# SparkFun_FreeSoC2.net
KiCad netlist of a schematic drawn in EAGLE
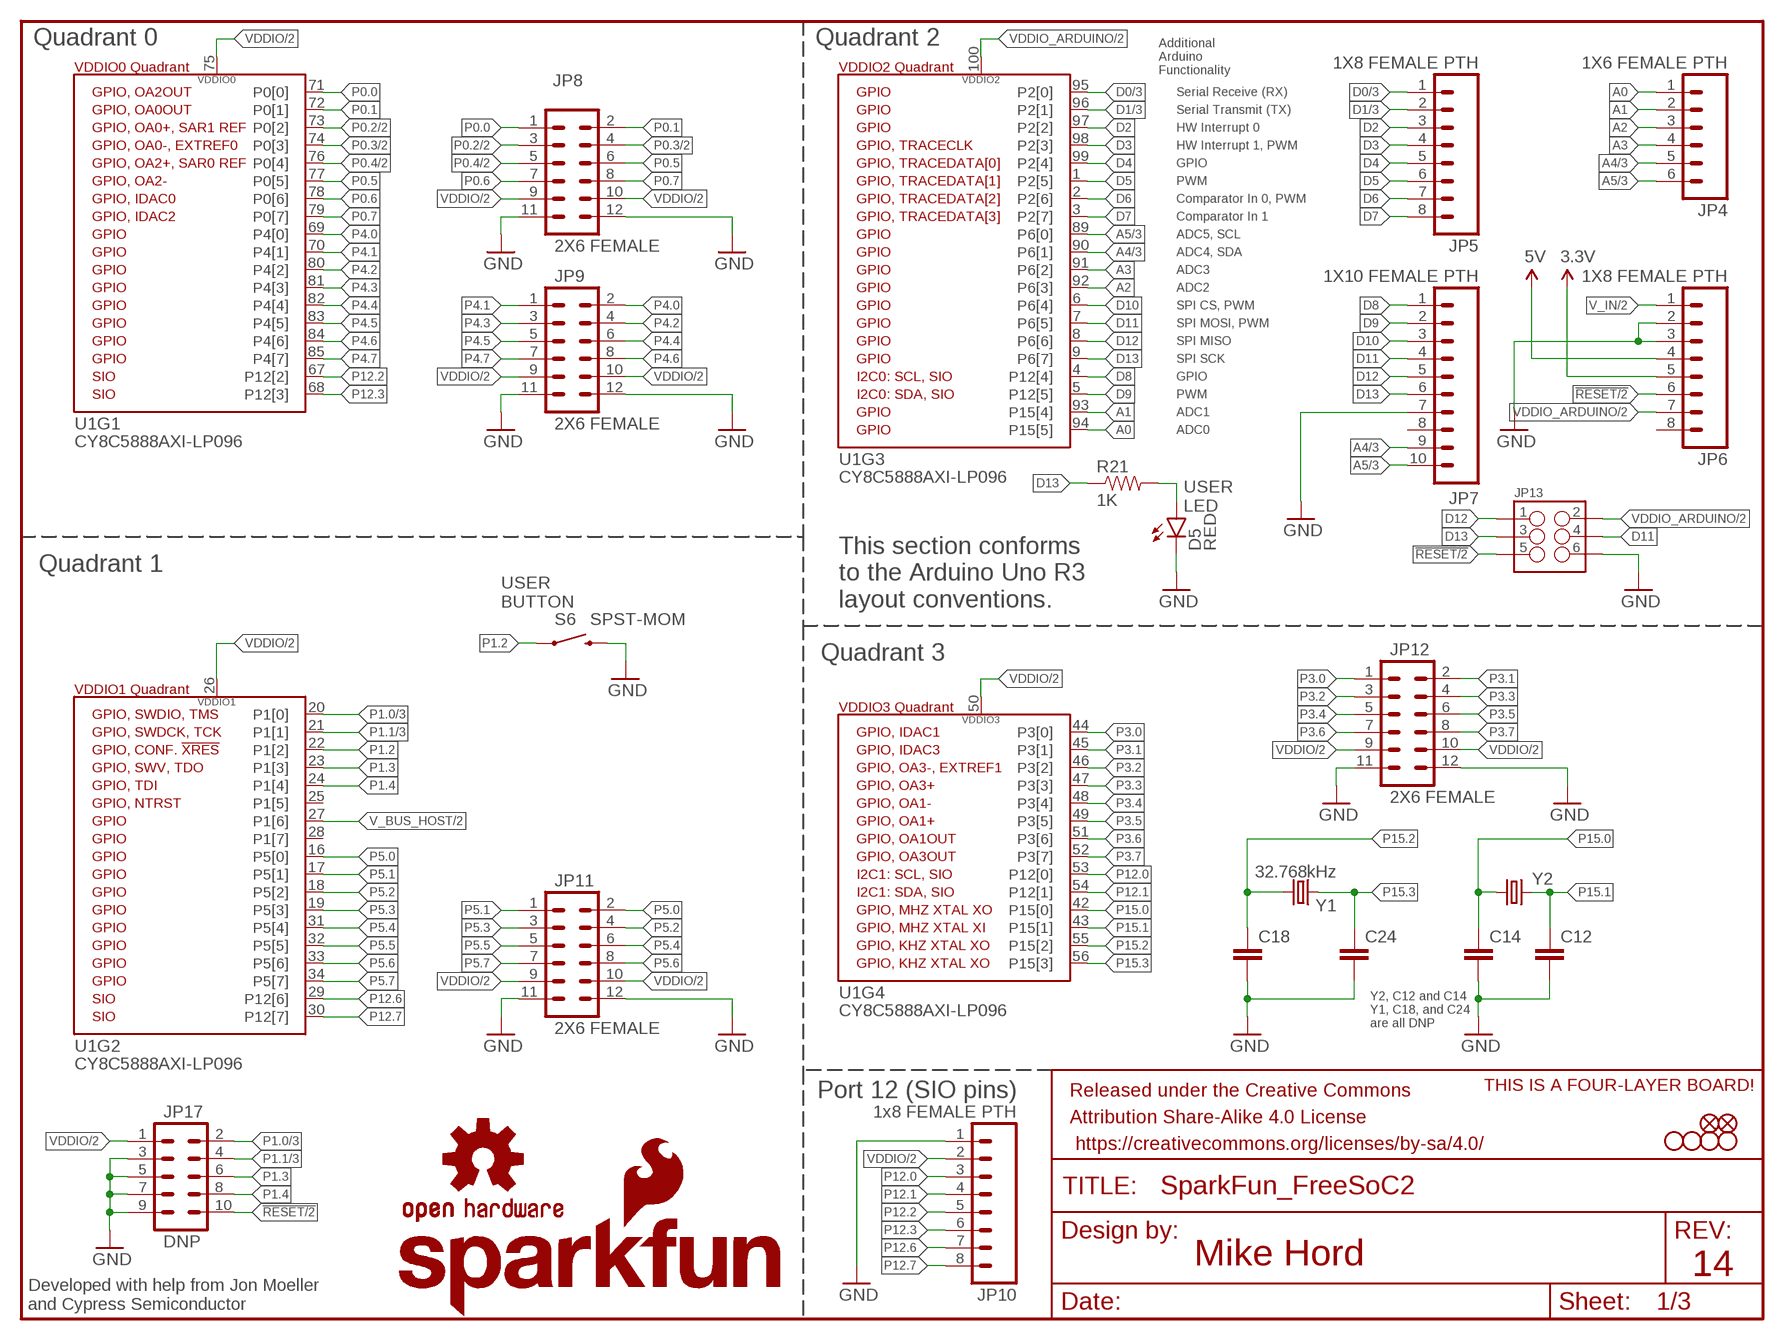
[diagram p0: schematic, sheet 1]
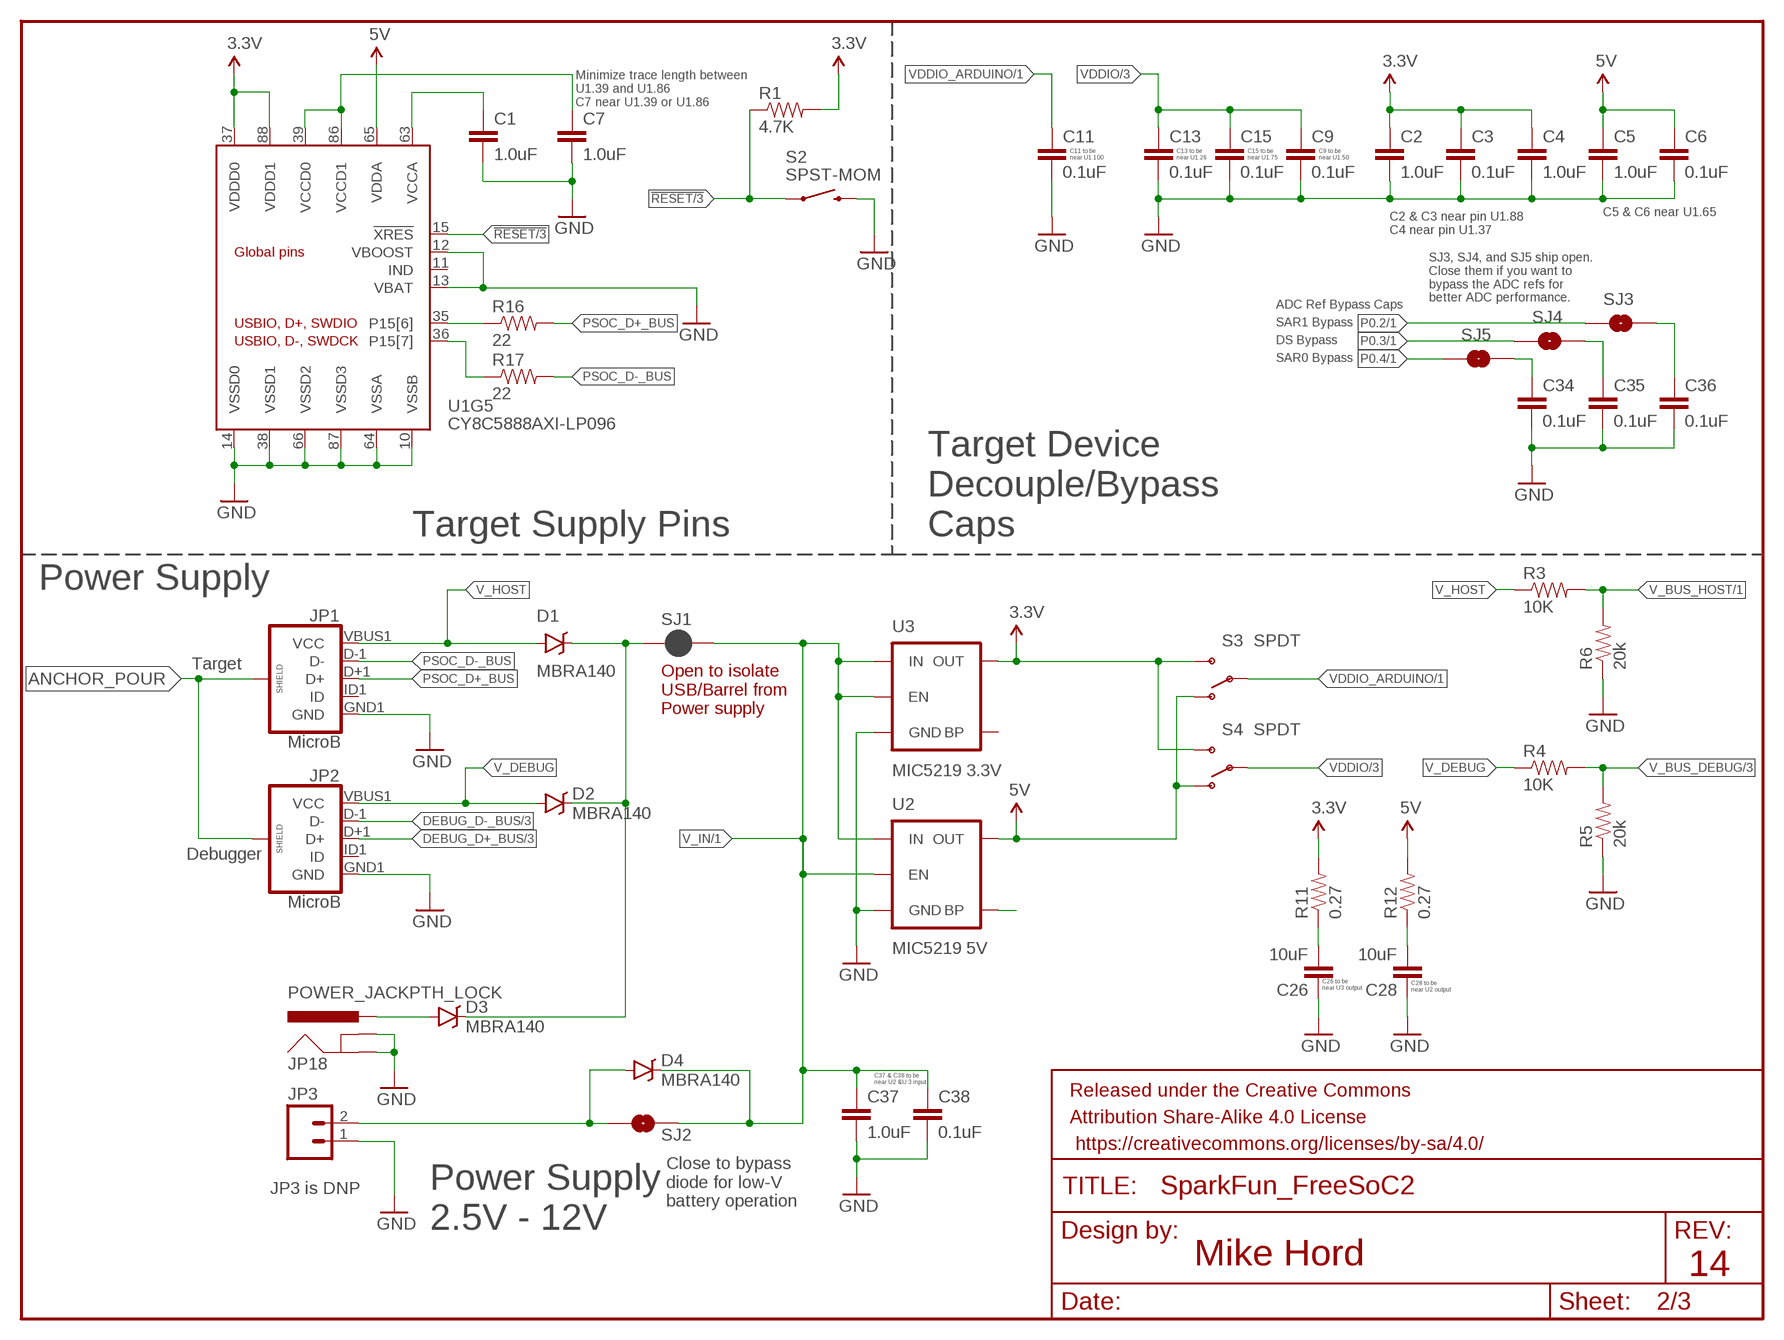
[diagram p1: schematic, sheet 2]
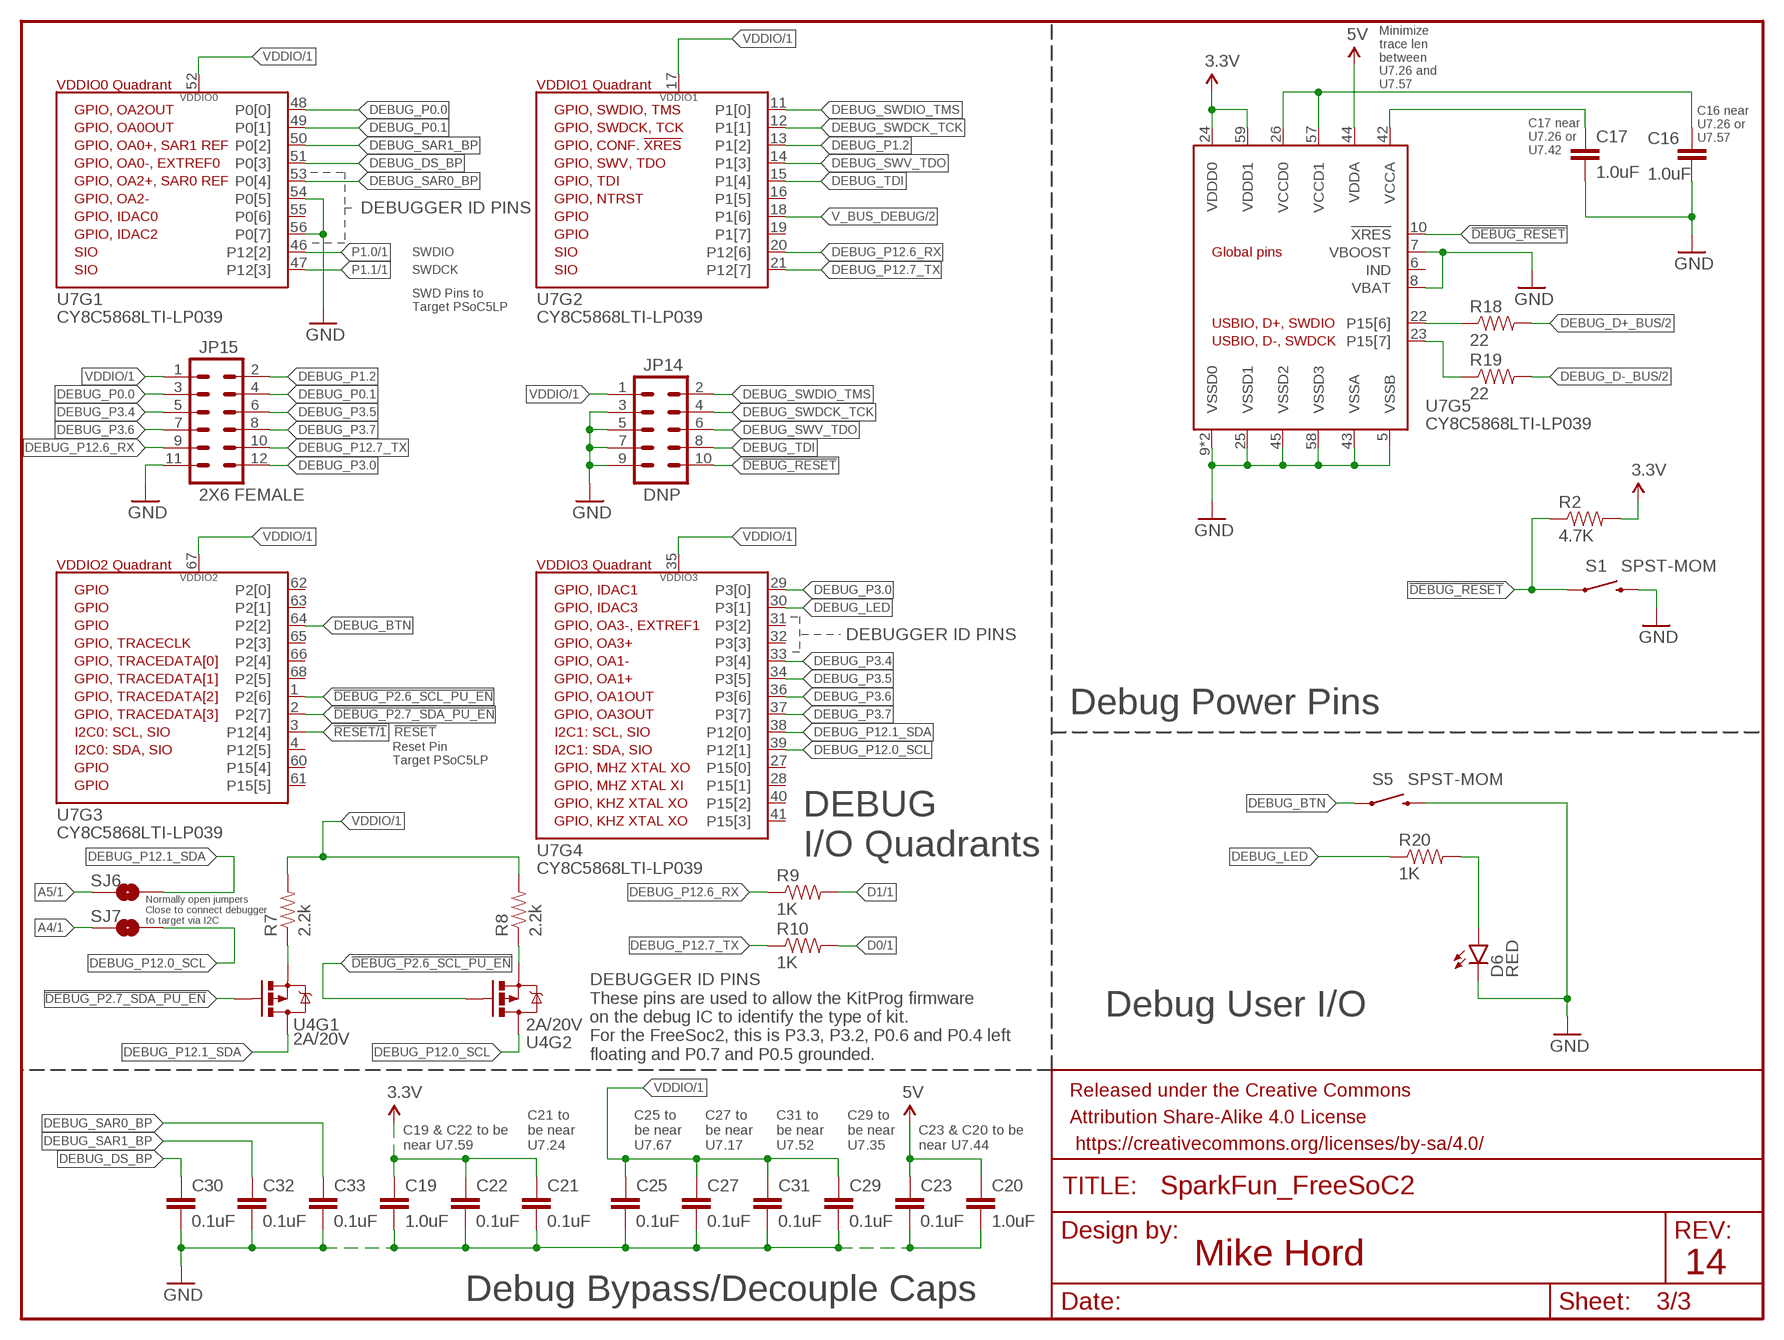
[diagram p2: schematic, sheet 3]

(export (version "E")
  (design (tool "Eeschema 10.0.6"))
  (components
    (comp (ref "C12")
      (value "CAPPTH")
      (footprint "eagle-import:CAP-PTH-SMALL")
      (libsource (lib "eagle-import") (part "CAPPTH"))
    )
    (comp (ref "C14")
      (value "CAPPTH")
      (footprint "eagle-import:CAP-PTH-SMALL")
      (libsource (lib "eagle-import") (part "CAPPTH"))
    )
    (comp (ref "C18")
      (value "CAPPTH")
      (footprint "eagle-import:CAP-PTH-SMALL")
      (libsource (lib "eagle-import") (part "CAPPTH"))
    )
    (comp (ref "C24")
      (value "CAPPTH")
      (footprint "eagle-import:CAP-PTH-SMALL")
      (libsource (lib "eagle-import") (part "CAPPTH"))
    )
    (comp (ref "D5")
      (value "RED")
      (footprint "eagle-import:LED-0603")
      (libsource (lib "eagle-import") (part "LED-RED0603"))
    )
    (comp (ref "FID1")
      (value "FIDUCIAL1X2")
      (footprint "eagle-import:FIDUCIAL-1X2")
      (libsource (lib "eagle-import") (part "FIDUCIAL1X2"))
    )
    (comp (ref "FID2")
      (value "FIDUCIAL1X2")
      (footprint "eagle-import:FIDUCIAL-1X2")
      (libsource (lib "eagle-import") (part "FIDUCIAL1X2"))
    )
    (comp (ref "FRAME3")
      (value "FRAME-LETTERNO_PACKAGE")
      (footprint "eagle-import:DUMMY")
      (fields (field (name "DESIGNER") "Nobody"))
      (libsource (lib "eagle-import") (part "FRAME-LETTERNO_PACKAGE"))
    )
    (comp (ref "JP4")
      (value "1X6 FEMALE PTH")
      (footprint "eagle-import:1X06-SIP_LOCK")
      (libsource (lib "eagle-import") (part "M06SIP_LOCK"))
    )
    (comp (ref "JP5")
      (value "1X8 FEMALE PTH")
      (footprint "eagle-import:1X08_LOCK")
      (libsource (lib "eagle-import") (part "M08LOCK"))
    )
    (comp (ref "JP6")
      (value "1X8 FEMALE PTH")
      (footprint "eagle-import:1X08_LOCK")
      (libsource (lib "eagle-import") (part "M08LOCK"))
    )
    (comp (ref "JP7")
      (value "1X10 FEMALE PTH")
      (footprint "eagle-import:1X10_LOCK")
      (libsource (lib "eagle-import") (part "M10LOCK"))
    )
    (comp (ref "JP8")
      (value "2X6 FEMALE")
      (footprint "eagle-import:2X6")
      (libsource (lib "eagle-import") (part "M06X2PTH_FEMALE"))
    )
    (comp (ref "JP9")
      (value "2X6 FEMALE")
      (footprint "eagle-import:2X6")
      (libsource (lib "eagle-import") (part "M06X2PTH_FEMALE"))
    )
    (comp (ref "JP10")
      (value "1x8 FEMALE PTH")
      (footprint "eagle-import:1X08_LOCK")
      (libsource (lib "eagle-import") (part "M08LOCK"))
    )
    (comp (ref "JP11")
      (value "2X6 FEMALE")
      (footprint "eagle-import:2X6")
      (libsource (lib "eagle-import") (part "M06X2PTH_FEMALE"))
    )
    (comp (ref "JP12")
      (value "2X6 FEMALE")
      (footprint "eagle-import:2X6")
      (libsource (lib "eagle-import") (part "M06X2PTH_FEMALE"))
    )
    (comp (ref "JP13")
      (value "M03X22X3_SILK_MALE_PTH")
      (footprint "eagle-import:2X3")
      (libsource (lib "eagle-import") (part "M03X22X3_SILK_MALE_PTH"))
    )
    (comp (ref "JP17")
      (value "DNP")
      (footprint "eagle-import:2X5_PTH_SILK_.05")
      (libsource (lib "eagle-import") (part "M05X20.05_IN_PTH_SILK"))
    )
    (comp (ref "LOGO1")
      (value "SFE_LOGO_NAME_FLAME.2_INCH")
      (footprint "eagle-import:SFE_LOGO_NAME_FLAME_.2")
      (libsource (lib "eagle-import") (part "SFE_LOGO_NAME_FLAME.2_INCH"))
    )
    (comp (ref "LOGO2")
      (value "OSHW-LOGOS")
      (footprint "eagle-import:OSHW-LOGO-S")
      (libsource (lib "eagle-import") (part "OSHW-LOGOS"))
    )
    (comp (ref "R21")
      (value "1K")
      (footprint "eagle-import:0603-RES@1")
      (libsource (lib "eagle-import") (part "1KOHM1/10W1%(0603)"))
    )
    (comp (ref "S6")
      (value "SPST-MOM")
      (footprint "eagle-import:TACTILE-SWITCH-SMD")
      (libsource (lib "eagle-import") (part "SWITCH-MOMENTARY-2SMD"))
    )
    (comp (ref "STANDOFF1")
      (value "STAND-OFF")
      (footprint "eagle-import:STAND-OFF")
      (libsource (lib "eagle-import") (part "STAND-OFF"))
    )
    (comp (ref "STANDOFF2")
      (value "STAND-OFF")
      (footprint "eagle-import:STAND-OFF")
      (libsource (lib "eagle-import") (part "STAND-OFF"))
    )
    (comp (ref "STANDOFF3")
      (value "STAND-OFF")
      (footprint "eagle-import:STAND-OFF")
      (libsource (lib "eagle-import") (part "STAND-OFF"))
    )
    (comp (ref "STANDOFF4")
      (value "STAND-OFF")
      (footprint "eagle-import:STAND-OFF")
      (libsource (lib "eagle-import") (part "STAND-OFF"))
    )
    (comp (ref "U$1")
      (value "FOUR_LAYER_WARNING")
      (footprint "eagle-import:FOUR_LAYER_WARNING")
      (libsource (lib "eagle-import") (part "FOUR_LAYER_WARNING"))
    )
    (comp (ref "U1")
      (value "CY8C5888AXI-LP096")
      (footprint "eagle-import:TQFP-100-14X14MM")
      (libsource (lib "eagle-import") (part "PSOC_5LP_100QFP"))
    )
    (comp (ref "Y1")
      (value "32.768kHz")
      (footprint "eagle-import:TC26H")
      (libsource (lib "eagle-import") (part "CRYSTALTC26H"))
    )
    (comp (ref "Y2")
      (value "CRYSTALHC49US")
      (footprint "eagle-import:HC49US")
      (libsource (lib "eagle-import") (part "CRYSTALHC49US"))
    )
    (comp (ref "C16")
      (value "1.0uF")
      (footprint "eagle-import:0402-CAP")
      (libsource (lib "eagle-import") (part "1.0UF-16V-10%(0402)"))
    )
    (comp (ref "C17")
      (value "1.0uF")
      (footprint "eagle-import:0402-CAP")
      (libsource (lib "eagle-import") (part "1.0UF-16V-10%(0402)"))
    )
    (comp (ref "C19")
      (value "1.0uF")
      (footprint "eagle-import:0402-CAP")
      (libsource (lib "eagle-import") (part "1.0UF-16V-10%(0402)"))
    )
    (comp (ref "C20")
      (value "1.0uF")
      (footprint "eagle-import:0402-CAP")
      (libsource (lib "eagle-import") (part "1.0UF-16V-10%(0402)"))
    )
    (comp (ref "C21")
      (value "0.1uF")
      (footprint "eagle-import:0402-CAP")
      (libsource (lib "eagle-import") (part "0.1UF-16V(+-10%)(0402)"))
    )
    (comp (ref "C22")
      (value "0.1uF")
      (footprint "eagle-import:0402-CAP")
      (libsource (lib "eagle-import") (part "0.1UF-16V(+-10%)(0402)"))
    )
    (comp (ref "C23")
      (value "0.1uF")
      (footprint "eagle-import:0402-CAP")
      (libsource (lib "eagle-import") (part "0.1UF-16V(+-10%)(0402)"))
    )
    (comp (ref "C25")
      (value "0.1uF")
      (footprint "eagle-import:0402-CAP")
      (libsource (lib "eagle-import") (part "0.1UF-16V(+-10%)(0402)"))
    )
    (comp (ref "C27")
      (value "0.1uF")
      (footprint "eagle-import:0402-CAP")
      (libsource (lib "eagle-import") (part "0.1UF-16V(+-10%)(0402)"))
    )
    (comp (ref "C29")
      (value "0.1uF")
      (footprint "eagle-import:0402-CAP")
      (libsource (lib "eagle-import") (part "0.1UF-16V(+-10%)(0402)"))
    )
    (comp (ref "C30")
      (value "0.1uF")
      (footprint "eagle-import:0402-CAP")
      (libsource (lib "eagle-import") (part "0.1UF-16V(+-10%)(0402)"))
    )
    (comp (ref "C31")
      (value "0.1uF")
      (footprint "eagle-import:0402-CAP")
      (libsource (lib "eagle-import") (part "0.1UF-16V(+-10%)(0402)"))
    )
    (comp (ref "C32")
      (value "0.1uF")
      (footprint "eagle-import:0402-CAP")
      (libsource (lib "eagle-import") (part "0.1UF-16V(+-10%)(0402)"))
    )
    (comp (ref "C33")
      (value "0.1uF")
      (footprint "eagle-import:0402-CAP")
      (libsource (lib "eagle-import") (part "0.1UF-16V(+-10%)(0402)"))
    )
    (comp (ref "D6")
      (value "RED")
      (footprint "eagle-import:LED-0603")
      (libsource (lib "eagle-import") (part "LED-RED0603"))
    )
    (comp (ref "FRAME1")
      (value "FRAME-LETTERNO_PACKAGE")
      (footprint "eagle-import:DUMMY")
      (fields (field (name "DESIGNER") "Nobody"))
      (libsource (lib "eagle-import") (part "FRAME-LETTERNO_PACKAGE"))
    )
    (comp (ref "JP14")
      (value "DNP")
      (footprint "eagle-import:2X5_PTH_SILK_.05")
      (libsource (lib "eagle-import") (part "M05X20.05_IN_PTH_SILK"))
    )
    (comp (ref "JP15")
      (value "2X6 FEMALE")
      (footprint "eagle-import:2X6")
      (libsource (lib "eagle-import") (part "M06X2PTH_FEMALE"))
    )
    (comp (ref "R2")
      (value "4.7K")
      (footprint "eagle-import:0603-RES")
      (libsource (lib "eagle-import") (part "4.7KOHM-1/10W-1%(0603)"))
    )
    (comp (ref "R7")
      (value "2.2k")
      (footprint "eagle-import:0603-RES")
      (libsource (lib "eagle-import") (part "2.2KOHM-1/10W-1%(0603)"))
    )
    (comp (ref "R8")
      (value "2.2k")
      (footprint "eagle-import:0603-RES")
      (libsource (lib "eagle-import") (part "2.2KOHM-1/10W-1%(0603)"))
    )
    (comp (ref "R9")
      (value "1K")
      (footprint "eagle-import:0603-RES@1")
      (libsource (lib "eagle-import") (part "1KOHM1/10W1%(0603)"))
    )
    (comp (ref "R10")
      (value "1K")
      (footprint "eagle-import:0603-RES@1")
      (libsource (lib "eagle-import") (part "1KOHM1/10W1%(0603)"))
    )
    (comp (ref "R18")
      (value "22")
      (footprint "eagle-import:0402-RES")
      (libsource (lib "eagle-import") (part "22OHM1/10W1%(0402)"))
    )
    (comp (ref "R19")
      (value "22")
      (footprint "eagle-import:0402-RES")
      (libsource (lib "eagle-import") (part "22OHM1/10W1%(0402)"))
    )
    (comp (ref "R20")
      (value "1K")
      (footprint "eagle-import:0603-RES@1")
      (libsource (lib "eagle-import") (part "1KOHM1/10W1%(0603)"))
    )
    (comp (ref "S1")
      (value "SPST-MOM")
      (footprint "eagle-import:TACTILE-SWITCH-SMD")
      (libsource (lib "eagle-import") (part "SWITCH-MOMENTARY-2SMD"))
    )
    (comp (ref "S5")
      (value "SPST-MOM")
      (footprint "eagle-import:TACTILE-SWITCH-SMD")
      (libsource (lib "eagle-import") (part "SWITCH-MOMENTARY-2SMD"))
    )
    (comp (ref "SJ6")
      (value "JUMPER-PAD-2-NO")
      (footprint "eagle-import:PAD-JUMPER-2-NO_NO_SILK")
      (libsource (lib "eagle-import") (part "JUMPER-PAD-2-NO"))
    )
    (comp (ref "SJ7")
      (value "JUMPER-PAD-2-NO")
      (footprint "eagle-import:PAD-JUMPER-2-NO_NO_SILK")
      (libsource (lib "eagle-import") (part "JUMPER-PAD-2-NO"))
    )
    (comp (ref "U4")
      (value "2A/20V")
      (footprint "eagle-import:SOT26")
      (libsource (lib "eagle-import") (part "MOSFET-PCHANNEL_DUALSOT26"))
    )
    (comp (ref "U7")
      (value "CY8C5868LTI-LP039")
      (footprint "eagle-import:QFN-68")
      (libsource (lib "eagle-import") (part "PSOC_5LP_68QFN"))
    )
    (comp (ref "C1")
      (value "1.0uF")
      (footprint "eagle-import:0402-CAP")
      (libsource (lib "eagle-import") (part "1.0UF-16V-10%(0402)"))
    )
    (comp (ref "C2")
      (value "1.0uF")
      (footprint "eagle-import:0402-CAP")
      (libsource (lib "eagle-import") (part "1.0UF-16V-10%(0402)"))
    )
    (comp (ref "C3")
      (value "0.1uF")
      (footprint "eagle-import:0402-CAP")
      (libsource (lib "eagle-import") (part "0.1UF-16V(+-10%)(0402)"))
    )
    (comp (ref "C4")
      (value "1.0uF")
      (footprint "eagle-import:0402-CAP")
      (libsource (lib "eagle-import") (part "1.0UF-16V-10%(0402)"))
    )
    (comp (ref "C5")
      (value "1.0uF")
      (footprint "eagle-import:0402-CAP")
      (libsource (lib "eagle-import") (part "1.0UF-16V-10%(0402)"))
    )
    (comp (ref "C6")
      (value "0.1uF")
      (footprint "eagle-import:0402-CAP")
      (libsource (lib "eagle-import") (part "0.1UF-16V(+-10%)(0402)"))
    )
    (comp (ref "C7")
      (value "1.0uF")
      (footprint "eagle-import:0402-CAP")
      (libsource (lib "eagle-import") (part "1.0UF-16V-10%(0402)"))
    )
    (comp (ref "C9")
      (value "0.1uF")
      (footprint "eagle-import:0402-CAP")
      (libsource (lib "eagle-import") (part "0.1UF-16V(+-10%)(0402)"))
    )
    (comp (ref "C11")
      (value "0.1uF")
      (footprint "eagle-import:0402-CAP")
      (libsource (lib "eagle-import") (part "0.1UF-16V(+-10%)(0402)"))
    )
    (comp (ref "C13")
      (value "0.1uF")
      (footprint "eagle-import:0402-CAP")
      (libsource (lib "eagle-import") (part "0.1UF-16V(+-10%)(0402)"))
    )
    (comp (ref "C15")
      (value "0.1uF")
      (footprint "eagle-import:0402-CAP")
      (libsource (lib "eagle-import") (part "0.1UF-16V(+-10%)(0402)"))
    )
    (comp (ref "C26")
      (value "10uF")
      (footprint "eagle-import:0805-CAP")
      (libsource (lib "eagle-import") (part "10UF10V10%(0805)"))
    )
    (comp (ref "C28")
      (value "10uF")
      (footprint "eagle-import:0805-CAP")
      (libsource (lib "eagle-import") (part "10UF10V10%(0805)"))
    )
    (comp (ref "C34")
      (value "0.1uF")
      (footprint "eagle-import:0402-CAP")
      (libsource (lib "eagle-import") (part "0.1UF-16V(+-10%)(0402)"))
    )
    (comp (ref "C35")
      (value "0.1uF")
      (footprint "eagle-import:0402-CAP")
      (libsource (lib "eagle-import") (part "0.1UF-16V(+-10%)(0402)"))
    )
    (comp (ref "C36")
      (value "0.1uF")
      (footprint "eagle-import:0402-CAP")
      (libsource (lib "eagle-import") (part "0.1UF-16V(+-10%)(0402)"))
    )
    (comp (ref "C37")
      (value "1.0uF")
      (footprint "eagle-import:0603-CAP")
      (libsource (lib "eagle-import") (part "1.0UF-16V-10%(0603)"))
    )
    (comp (ref "C38")
      (value "0.1uF")
      (footprint "eagle-import:0603-CAP")
      (libsource (lib "eagle-import") (part "0.1UF-25V(+80/-20%)(0603)"))
    )
    (comp (ref "D1")
      (value "MBRA140")
      (footprint "eagle-import:SMA-DIODE")
      (libsource (lib "eagle-import") (part "MBRA140"))
    )
    (comp (ref "D2")
      (value "MBRA140")
      (footprint "eagle-import:SMA-DIODE")
      (libsource (lib "eagle-import") (part "MBRA140"))
    )
    (comp (ref "D3")
      (value "MBRA140")
      (footprint "eagle-import:SMA-DIODE")
      (libsource (lib "eagle-import") (part "MBRA140"))
    )
    (comp (ref "D4")
      (value "MBRA140")
      (footprint "eagle-import:SMA-DIODE")
      (libsource (lib "eagle-import") (part "MBRA140"))
    )
    (comp (ref "FRAME2")
      (value "FRAME-LETTERNO_PACKAGE")
      (footprint "eagle-import:DUMMY")
      (fields (field (name "DESIGNER") "Nobody"))
      (libsource (lib "eagle-import") (part "FRAME-LETTERNO_PACKAGE"))
    )
    (comp (ref "JP1")
      (value "MicroB")
      (footprint "eagle-import:USB-B-MICRO-SMD_V03")
      (libsource (lib "eagle-import") (part "USB_MICROB_PLUGCONN-11752"))
    )
    (comp (ref "JP2")
      (value "MicroB")
      (footprint "eagle-import:USB-B-MICRO-SMD_V03")
      (libsource (lib "eagle-import") (part "USB_MICROB_PLUGCONN-11752"))
    )
    (comp (ref "JP3")
      (value "M02JST-PTH-2")
      (footprint "eagle-import:JST-2-PTH")
      (libsource (lib "eagle-import") (part "M02JST-PTH-2"))
    )
    (comp (ref "JP18")
      (value "POWER_JACKPTH_LOCK")
      (footprint "eagle-import:POWER_JACK_PTH_LOCK")
      (libsource (lib "eagle-import") (part "POWER_JACKPTH_LOCK"))
    )
    (comp (ref "R1")
      (value "4.7K")
      (footprint "eagle-import:0603-RES")
      (libsource (lib "eagle-import") (part "4.7KOHM-1/10W-1%(0603)"))
    )
    (comp (ref "R3")
      (value "10K")
      (footprint "eagle-import:0603-RES")
      (libsource (lib "eagle-import") (part "10KOHM-1/10W-1%(0603)0603"))
    )
    (comp (ref "R4")
      (value "10K")
      (footprint "eagle-import:0603-RES")
      (libsource (lib "eagle-import") (part "10KOHM-1/10W-1%(0603)0603"))
    )
    (comp (ref "R5")
      (value "20k")
      (footprint "eagle-import:0603-RES")
      (libsource (lib "eagle-import") (part "20KOHM1/10W1%(0603)"))
    )
    (comp (ref "R6")
      (value "20k")
      (footprint "eagle-import:0603-RES")
      (libsource (lib "eagle-import") (part "20KOHM1/10W1%(0603)"))
    )
    (comp (ref "R11")
      (value "0.27")
      (footprint "eagle-import:0603-RES")
      (fields (field (name "PROD_ID") "RES-08787"))
      (libsource (lib "eagle-import") (part "0.27OHM-1/10W-1%(0603)"))
    )
    (comp (ref "R12")
      (value "0.27")
      (footprint "eagle-import:0603-RES")
      (fields (field (name "PROD_ID") "RES-08787"))
      (libsource (lib "eagle-import") (part "0.27OHM-1/10W-1%(0603)"))
    )
    (comp (ref "R16")
      (value "22")
      (footprint "eagle-import:0402-RES")
      (libsource (lib "eagle-import") (part "22OHM1/10W1%(0402)"))
    )
    (comp (ref "R17")
      (value "22")
      (footprint "eagle-import:0402-RES")
      (libsource (lib "eagle-import") (part "22OHM1/10W1%(0402)"))
    )
    (comp (ref "S2")
      (value "SPST-MOM")
      (footprint "eagle-import:TACTILE-SWITCH-SMD")
      (libsource (lib "eagle-import") (part "SWITCH-MOMENTARY-2SMD"))
    )
    (comp (ref "S3")
      (value "SPDT")
      (footprint "eagle-import:SWITCH-SPDT_LOCK.007S")
      (libsource (lib "eagle-import") (part "SWITCH-SPDTPTH_LOCK"))
    )
    (comp (ref "S4")
      (value "SPDT")
      (footprint "eagle-import:SWITCH-SPDT_LOCK.007S")
      (libsource (lib "eagle-import") (part "SWITCH-SPDTPTH_LOCK"))
    )
    (comp (ref "SJ1")
      (value "JUMPER-PAD-2-NC_BY_PASTE")
      (footprint "eagle-import:PAD-JUMPER-2-NC_BY_PASTE_YES_SILK")
      (libsource (lib "eagle-import") (part "JUMPER-PAD-2-NC_BY_PASTE"))
    )
    (comp (ref "SJ2")
      (value "JUMPER-PAD-2-NOYES_SILK")
      (footprint "eagle-import:PAD-JUMPER-2-NO_YES_SILK")
      (libsource (lib "eagle-import") (part "JUMPER-PAD-2-NOYES_SILK"))
    )
    (comp (ref "SJ3")
      (value "JUMPER-PAD-2-NO")
      (footprint "eagle-import:PAD-JUMPER-2-NO_NO_SILK")
      (libsource (lib "eagle-import") (part "JUMPER-PAD-2-NO"))
    )
    (comp (ref "SJ4")
      (value "JUMPER-PAD-2-NO")
      (footprint "eagle-import:PAD-JUMPER-2-NO_NO_SILK")
      (libsource (lib "eagle-import") (part "JUMPER-PAD-2-NO"))
    )
    (comp (ref "SJ5")
      (value "JUMPER-PAD-2-NO")
      (footprint "eagle-import:PAD-JUMPER-2-NO_NO_SILK")
      (libsource (lib "eagle-import") (part "JUMPER-PAD-2-NO"))
    )
    (comp (ref "U2")
      (value "MIC5219 5V")
      (footprint "eagle-import:SOT23-5")
      (libsource (lib "eagle-import") (part "V_REG_MIC52195V"))
    )
    (comp (ref "U3")
      (value "MIC5219 3.3V")
      (footprint "eagle-import:SOT23-5")
      (libsource (lib "eagle-import") (part "V_REG_MIC52193.3V"))
    )
  )
  (nets
    (net (code "1") (name "3.3V") (class "Default")
      (node (ref "C19") (pin "1") (pinfunction "1_1") (pintype "passive"))
      (node (ref "C2") (pin "1") (pinfunction "1_1") (pintype "passive"))
      (node (ref "C21") (pin "1") (pinfunction "1_1") (pintype "passive"))
      (node (ref "C22") (pin "1") (pinfunction "1_1") (pintype "passive"))
      (node (ref "C3") (pin "1") (pinfunction "1_1") (pintype "passive"))
      (node (ref "C4") (pin "1") (pinfunction "1_1") (pintype "passive"))
      (node (ref "JP6") (pin "5") (pinfunction "5_5") (pintype "passive"))
      (node (ref "R1") (pin "2") (pinfunction "2_2") (pintype "passive"))
      (node (ref "R11") (pin "2") (pinfunction "2_2") (pintype "passive"))
      (node (ref "R2") (pin "2") (pinfunction "2_2") (pintype "passive"))
      (node (ref "S3") (pin "3") (pinfunction "S_3") (pintype "passive"))
      (node (ref "S4") (pin "3") (pinfunction "S_3") (pintype "passive"))
      (node (ref "U1") (pin "37") (pinfunction "VDDD0_37") (pintype "bidirectional"))
      (node (ref "U1") (pin "88") (pinfunction "VDDD1_88") (pintype "bidirectional"))
      (node (ref "U3") (pin "5") (pinfunction "OUT_5") (pintype "passive"))
      (node (ref "U7") (pin "24") (pinfunction "VDDD0_24") (pintype "bidirectional"))
      (node (ref "U7") (pin "59") (pinfunction "VDDD1_59") (pintype "bidirectional"))
    )
    (net (code "2") (name "5V") (class "Default")
      (node (ref "C20") (pin "1") (pinfunction "1_1") (pintype "passive"))
      (node (ref "C23") (pin "1") (pinfunction "1_1") (pintype "passive"))
      (node (ref "C5") (pin "1") (pinfunction "1_1") (pintype "passive"))
      (node (ref "C6") (pin "1") (pinfunction "1_1") (pintype "passive"))
      (node (ref "JP6") (pin "4") (pinfunction "4_4") (pintype "passive"))
      (node (ref "R12") (pin "2") (pinfunction "2_2") (pintype "passive"))
      (node (ref "S3") (pin "1") (pinfunction "O_1") (pintype "passive"))
      (node (ref "S4") (pin "1") (pinfunction "O_1") (pintype "passive"))
      (node (ref "U1") (pin "65") (pinfunction "VDDA_65") (pintype "bidirectional"))
      (node (ref "U2") (pin "5") (pinfunction "OUT_5") (pintype "passive"))
      (node (ref "U7") (pin "44") (pinfunction "VDDA_44") (pintype "bidirectional"))
    )
    (net (code "3") (name "A0") (class "Default")
      (node (ref "JP4") (pin "1") (pinfunction "1_1") (pintype "passive"))
      (node (ref "U1") (pin "94") (pinfunction "P15[5]_94") (pintype "bidirectional"))
    )
    (net (code "4") (name "A1") (class "Default")
      (node (ref "JP4") (pin "2") (pinfunction "2_2") (pintype "passive"))
      (node (ref "U1") (pin "93") (pinfunction "P15[4]_93") (pintype "bidirectional"))
    )
    (net (code "5") (name "A2") (class "Default")
      (node (ref "JP4") (pin "3") (pinfunction "3_3") (pintype "passive"))
      (node (ref "U1") (pin "92") (pinfunction "P6[3]_92") (pintype "bidirectional"))
    )
    (net (code "6") (name "A3") (class "Default")
      (node (ref "JP4") (pin "4") (pinfunction "4_4") (pintype "passive"))
      (node (ref "U1") (pin "91") (pinfunction "P6[2]_91") (pintype "bidirectional"))
    )
    (net (code "7") (name "A4") (class "Default")
      (node (ref "JP4") (pin "5") (pinfunction "5_5") (pintype "passive"))
      (node (ref "JP7") (pin "9") (pinfunction "9_9") (pintype "passive"))
      (node (ref "SJ7") (pin "1") (pinfunction "1_1") (pintype "passive"))
      (node (ref "U1") (pin "90") (pinfunction "P6[1]_90") (pintype "bidirectional"))
    )
    (net (code "8") (name "A5") (class "Default")
      (node (ref "JP4") (pin "6") (pinfunction "6_6") (pintype "passive"))
      (node (ref "JP7") (pin "10") (pinfunction "10_10") (pintype "passive"))
      (node (ref "SJ6") (pin "1") (pinfunction "1_1") (pintype "passive"))
      (node (ref "U1") (pin "89") (pinfunction "P6[0]_89") (pintype "bidirectional"))
    )
    (net (code "9") (name "ANCHOR_POUR") (class "Default")
      (node (ref "JP1") (pin "SHIELD1") (pinfunction "SHIELD_SHIELD1") (pintype "bidirectional"))
      (node (ref "JP1") (pin "SHIELD2") (pinfunction "SHIELD_SHIELD2") (pintype "bidirectional"))
      (node (ref "JP1") (pin "SHIELD3") (pinfunction "SHIELD_SHIELD3") (pintype "bidirectional"))
      (node (ref "JP2") (pin "SHIELD1") (pinfunction "SHIELD_SHIELD1") (pintype "bidirectional"))
      (node (ref "JP2") (pin "SHIELD2") (pinfunction "SHIELD_SHIELD2") (pintype "bidirectional"))
      (node (ref "JP2") (pin "SHIELD3") (pinfunction "SHIELD_SHIELD3") (pintype "bidirectional"))
    )
    (net (code "10") (name "D0") (class "Default")
      (node (ref "JP5") (pin "1") (pinfunction "1_1") (pintype "passive"))
      (node (ref "R10") (pin "2") (pinfunction "2_2") (pintype "passive"))
      (node (ref "U1") (pin "95") (pinfunction "P2[0]_95") (pintype "bidirectional"))
    )
    (net (code "11") (name "D1") (class "Default")
      (node (ref "JP5") (pin "2") (pinfunction "2_2") (pintype "passive"))
      (node (ref "R9") (pin "2") (pinfunction "2_2") (pintype "passive"))
      (node (ref "U1") (pin "96") (pinfunction "P2[1]_96") (pintype "bidirectional"))
    )
    (net (code "12") (name "D2") (class "Default")
      (node (ref "JP5") (pin "3") (pinfunction "3_3") (pintype "passive"))
      (node (ref "U1") (pin "97") (pinfunction "P2[2]_97") (pintype "bidirectional"))
    )
    (net (code "13") (name "D3") (class "Default")
      (node (ref "JP5") (pin "4") (pinfunction "4_4") (pintype "passive"))
      (node (ref "U1") (pin "98") (pinfunction "P2[3]_98") (pintype "bidirectional"))
    )
    (net (code "14") (name "D4") (class "Default")
      (node (ref "JP5") (pin "5") (pinfunction "5_5") (pintype "passive"))
      (node (ref "U1") (pin "99") (pinfunction "P2[4]_99") (pintype "bidirectional"))
    )
    (net (code "15") (name "D5") (class "Default")
      (node (ref "JP5") (pin "6") (pinfunction "6_6") (pintype "passive"))
      (node (ref "U1") (pin "1") (pinfunction "P2[5]_1") (pintype "bidirectional"))
    )
    (net (code "16") (name "D6") (class "Default")
      (node (ref "JP5") (pin "7") (pinfunction "7_7") (pintype "passive"))
      (node (ref "U1") (pin "2") (pinfunction "P2[6]_2") (pintype "bidirectional"))
    )
    (net (code "17") (name "D7") (class "Default")
      (node (ref "JP5") (pin "8") (pinfunction "8_8") (pintype "passive"))
      (node (ref "U1") (pin "3") (pinfunction "P2[7]_3") (pintype "bidirectional"))
    )
    (net (code "18") (name "D8") (class "Default")
      (node (ref "JP7") (pin "1") (pinfunction "1_1") (pintype "passive"))
      (node (ref "U1") (pin "4") (pinfunction "P12[4]_4") (pintype "bidirectional"))
    )
    (net (code "19") (name "D9") (class "Default")
      (node (ref "JP7") (pin "2") (pinfunction "2_2") (pintype "passive"))
      (node (ref "U1") (pin "5") (pinfunction "P12[5]_5") (pintype "bidirectional"))
    )
    (net (code "20") (name "D10") (class "Default")
      (node (ref "JP7") (pin "3") (pinfunction "3_3") (pintype "passive"))
      (node (ref "U1") (pin "6") (pinfunction "P6[4]_6") (pintype "bidirectional"))
    )
    (net (code "21") (name "D11") (class "Default")
      (node (ref "JP13") (pin "4") (pinfunction "4_4") (pintype "bidirectional"))
      (node (ref "JP7") (pin "4") (pinfunction "4_4") (pintype "passive"))
      (node (ref "U1") (pin "7") (pinfunction "P6[5]_7") (pintype "bidirectional"))
    )
    (net (code "22") (name "D12") (class "Default")
      (node (ref "JP13") (pin "1") (pinfunction "1_1") (pintype "bidirectional"))
      (node (ref "JP7") (pin "5") (pinfunction "5_5") (pintype "passive"))
      (node (ref "U1") (pin "8") (pinfunction "P6[6]_8") (pintype "bidirectional"))
    )
    (net (code "23") (name "D13") (class "Default")
      (node (ref "JP13") (pin "3") (pinfunction "3_3") (pintype "bidirectional"))
      (node (ref "JP7") (pin "6") (pinfunction "6_6") (pintype "passive"))
      (node (ref "R21") (pin "1") (pinfunction "1_1") (pintype "passive"))
      (node (ref "U1") (pin "9") (pinfunction "P6[7]_9") (pintype "bidirectional"))
    )
    (net (code "24") (name "DEBUG_BTN") (class "Default")
      (node (ref "S5") (pin "1") (pinfunction "1_1") (pintype "passive"))
      (node (ref "U7") (pin "64") (pinfunction "P2[2]_64") (pintype "bidirectional"))
    )
    (net (code "25") (name "DEBUG_D+_BUS") (class "Default")
      (node (ref "JP2") (pin "D+1") (pinfunction "D+_D+1") (pintype "bidirectional"))
      (node (ref "R18") (pin "2") (pinfunction "2_2") (pintype "passive"))
    )
    (net (code "26") (name "DEBUG_D-_BUS") (class "Default")
      (node (ref "JP2") (pin "D-1") (pinfunction "D-_D-1") (pintype "bidirectional"))
      (node (ref "R19") (pin "2") (pinfunction "2_2") (pintype "passive"))
    )
    (net (code "27") (name "DEBUG_DS_BP") (class "Default")
      (node (ref "C30") (pin "1") (pinfunction "1_1") (pintype "passive"))
      (node (ref "U7") (pin "51") (pinfunction "P0[3]_51") (pintype "bidirectional"))
    )
    (net (code "28") (name "DEBUG_LED") (class "Default")
      (node (ref "R20") (pin "1") (pinfunction "1_1") (pintype "passive"))
      (node (ref "U7") (pin "30") (pinfunction "P3[1]_30") (pintype "bidirectional"))
    )
    (net (code "29") (name "DEBUG_P0.0") (class "Default")
      (node (ref "JP15") (pin "3") (pinfunction "3_3") (pintype "passive"))
      (node (ref "U7") (pin "48") (pinfunction "P0[0]_48") (pintype "bidirectional"))
    )
    (net (code "30") (name "DEBUG_P0.1") (class "Default")
      (node (ref "JP15") (pin "4") (pinfunction "4_4") (pintype "passive"))
      (node (ref "U7") (pin "49") (pinfunction "P0[1]_49") (pintype "bidirectional"))
    )
    (net (code "31") (name "DEBUG_P1.2") (class "Default")
      (node (ref "JP15") (pin "2") (pinfunction "2_2") (pintype "passive"))
      (node (ref "U7") (pin "13") (pinfunction "P1[2]_13") (pintype "bidirectional"))
    )
    (net (code "32") (name "DEBUG_P3.0") (class "Default")
      (node (ref "JP15") (pin "12") (pinfunction "12_12") (pintype "passive"))
      (node (ref "U7") (pin "29") (pinfunction "P3[0]_29") (pintype "bidirectional"))
    )
    (net (code "33") (name "DEBUG_P3.4") (class "Default")
      (node (ref "JP15") (pin "5") (pinfunction "5_5") (pintype "passive"))
      (node (ref "U7") (pin "33") (pinfunction "P3[4]_33") (pintype "bidirectional"))
    )
    (net (code "34") (name "DEBUG_P3.5") (class "Default")
      (node (ref "JP15") (pin "6") (pinfunction "6_6") (pintype "passive"))
      (node (ref "U7") (pin "34") (pinfunction "P3[5]_34") (pintype "bidirectional"))
    )
    (net (code "35") (name "DEBUG_P3.6") (class "Default")
      (node (ref "JP15") (pin "7") (pinfunction "7_7") (pintype "passive"))
      (node (ref "U7") (pin "36") (pinfunction "P3[6]_36") (pintype "bidirectional"))
    )
    (net (code "36") (name "DEBUG_P3.7") (class "Default")
      (node (ref "JP15") (pin "8") (pinfunction "8_8") (pintype "passive"))
      (node (ref "U7") (pin "37") (pinfunction "P3[7]_37") (pintype "bidirectional"))
    )
    (net (code "37") (name "DEBUG_P12.0_SCL") (class "Default")
      (node (ref "SJ7") (pin "2") (pinfunction "2_2") (pintype "passive"))
      (node (ref "U4") (pin "D2") (pinfunction "D_D2") (pintype "passive"))
      (node (ref "U7") (pin "39") (pinfunction "P12[1]_39") (pintype "bidirectional"))
    )
    (net (code "38") (name "DEBUG_P12.1_SDA") (class "Default")
      (node (ref "SJ6") (pin "2") (pinfunction "2_2") (pintype "passive"))
      (node (ref "U4") (pin "D1") (pinfunction "D_D1") (pintype "passive"))
      (node (ref "U7") (pin "38") (pinfunction "P12[0]_38") (pintype "bidirectional"))
    )
    (net (code "39") (name "DEBUG_P12.6_RX") (class "Default")
      (node (ref "JP15") (pin "9") (pinfunction "9_9") (pintype "passive"))
      (node (ref "R9") (pin "1") (pinfunction "1_1") (pintype "passive"))
      (node (ref "U7") (pin "20") (pinfunction "P12[6]_20") (pintype "bidirectional"))
    )
    (net (code "40") (name "DEBUG_P12.7_TX") (class "Default")
      (node (ref "JP15") (pin "10") (pinfunction "10_10") (pintype "passive"))
      (node (ref "R10") (pin "1") (pinfunction "1_1") (pintype "passive"))
      (node (ref "U7") (pin "21") (pinfunction "P12[7]_21") (pintype "bidirectional"))
    )
    (net (code "41") (name "DEBUG_SAR0_BP") (class "Default")
      (node (ref "C33") (pin "1") (pinfunction "1_1") (pintype "passive"))
      (node (ref "U7") (pin "53") (pinfunction "P0[4]_53") (pintype "bidirectional"))
    )
    (net (code "42") (name "DEBUG_SAR1_BP") (class "Default")
      (node (ref "C32") (pin "1") (pinfunction "1_1") (pintype "passive"))
      (node (ref "U7") (pin "50") (pinfunction "P0[2]_50") (pintype "bidirectional"))
    )
    (net (code "43") (name "DEBUG_SWDCK_TCK") (class "Default")
      (node (ref "JP14") (pin "4") (pinfunction "4_4") (pintype "passive"))
      (node (ref "U7") (pin "12") (pinfunction "P1[1]_12") (pintype "bidirectional"))
    )
    (net (code "44") (name "DEBUG_SWDIO_TMS") (class "Default")
      (node (ref "JP14") (pin "2") (pinfunction "2_2") (pintype "passive"))
      (node (ref "U7") (pin "11") (pinfunction "P1[0]_11") (pintype "bidirectional"))
    )
    (net (code "45") (name "DEBUG_SWV_TDO") (class "Default")
      (node (ref "JP14") (pin "6") (pinfunction "6_6") (pintype "passive"))
      (node (ref "U7") (pin "14") (pinfunction "P1[3]_14") (pintype "bidirectional"))
    )
    (net (code "46") (name "DEBUG_TDI") (class "Default")
      (node (ref "JP14") (pin "8") (pinfunction "8_8") (pintype "passive"))
      (node (ref "U7") (pin "15") (pinfunction "P1[4]_15") (pintype "bidirectional"))
    )
    (net (code "47") (name "GND") (class "Default")
      (node (ref "C1") (pin "2") (pinfunction "2_2") (pintype "passive"))
      (node (ref "C11") (pin "2") (pinfunction "2_2") (pintype "passive"))
      (node (ref "C12") (pin "2") (pinfunction "2_2") (pintype "passive"))
      (node (ref "C13") (pin "2") (pinfunction "2_2") (pintype "passive"))
      (node (ref "C14") (pin "2") (pinfunction "2_2") (pintype "passive"))
      (node (ref "C15") (pin "2") (pinfunction "2_2") (pintype "passive"))
      (node (ref "C16") (pin "2") (pinfunction "2_2") (pintype "passive"))
      (node (ref "C17") (pin "2") (pinfunction "2_2") (pintype "passive"))
      (node (ref "C18") (pin "2") (pinfunction "2_2") (pintype "passive"))
      (node (ref "C19") (pin "2") (pinfunction "2_2") (pintype "passive"))
      (node (ref "C2") (pin "2") (pinfunction "2_2") (pintype "passive"))
      (node (ref "C20") (pin "2") (pinfunction "2_2") (pintype "passive"))
      (node (ref "C21") (pin "2") (pinfunction "2_2") (pintype "passive"))
      (node (ref "C22") (pin "2") (pinfunction "2_2") (pintype "passive"))
      (node (ref "C23") (pin "2") (pinfunction "2_2") (pintype "passive"))
      (node (ref "C24") (pin "2") (pinfunction "2_2") (pintype "passive"))
      (node (ref "C25") (pin "2") (pinfunction "2_2") (pintype "passive"))
      (node (ref "C26") (pin "1") (pinfunction "1_1") (pintype "passive"))
      (node (ref "C27") (pin "2") (pinfunction "2_2") (pintype "passive"))
      (node (ref "C28") (pin "1") (pinfunction "1_1") (pintype "passive"))
      (node (ref "C29") (pin "2") (pinfunction "2_2") (pintype "passive"))
      (node (ref "C3") (pin "2") (pinfunction "2_2") (pintype "passive"))
      (node (ref "C30") (pin "2") (pinfunction "2_2") (pintype "passive"))
      (node (ref "C31") (pin "2") (pinfunction "2_2") (pintype "passive"))
      (node (ref "C32") (pin "2") (pinfunction "2_2") (pintype "passive"))
      (node (ref "C33") (pin "2") (pinfunction "2_2") (pintype "passive"))
      (node (ref "C34") (pin "2") (pinfunction "2_2") (pintype "passive"))
      (node (ref "C35") (pin "2") (pinfunction "2_2") (pintype "passive"))
      (node (ref "C36") (pin "2") (pinfunction "2_2") (pintype "passive"))
      (node (ref "C37") (pin "2") (pinfunction "2_2") (pintype "passive"))
      (node (ref "C38") (pin "2") (pinfunction "2_2") (pintype "passive"))
      (node (ref "C4") (pin "2") (pinfunction "2_2") (pintype "passive"))
      (node (ref "C5") (pin "2") (pinfunction "2_2") (pintype "passive"))
      (node (ref "C6") (pin "2") (pinfunction "2_2") (pintype "passive"))
      (node (ref "C7") (pin "2") (pinfunction "2_2") (pintype "passive"))
      (node (ref "C9") (pin "2") (pinfunction "2_2") (pintype "passive"))
      (node (ref "D5") (pin "C") (pinfunction "C_C") (pintype "passive"))
      (node (ref "D6") (pin "C") (pinfunction "C_C") (pintype "passive"))
      (node (ref "JP1") (pin "GND1") (pinfunction "GND_GND1") (pintype "bidirectional"))
      (node (ref "JP10") (pin "1") (pinfunction "1_1") (pintype "passive"))
      (node (ref "JP11") (pin "11") (pinfunction "11_11") (pintype "passive"))
      (node (ref "JP11") (pin "12") (pinfunction "12_12") (pintype "passive"))
      (node (ref "JP12") (pin "11") (pinfunction "11_11") (pintype "passive"))
      (node (ref "JP12") (pin "12") (pinfunction "12_12") (pintype "passive"))
      (node (ref "JP13") (pin "6") (pinfunction "6_6") (pintype "bidirectional"))
      (node (ref "JP14") (pin "3") (pinfunction "3_3") (pintype "passive"))
      (node (ref "JP14") (pin "5") (pinfunction "5_5") (pintype "passive"))
      (node (ref "JP14") (pin "7") (pinfunction "7_7") (pintype "passive"))
      (node (ref "JP14") (pin "9") (pinfunction "9_9") (pintype "passive"))
      (node (ref "JP15") (pin "11") (pinfunction "11_11") (pintype "passive"))
      (node (ref "JP17") (pin "3") (pinfunction "3_3") (pintype "passive"))
      (node (ref "JP17") (pin "5") (pinfunction "5_5") (pintype "passive"))
      (node (ref "JP17") (pin "7") (pinfunction "7_7") (pintype "passive"))
      (node (ref "JP17") (pin "9") (pinfunction "9_9") (pintype "passive"))
      (node (ref "JP18") (pin "GND") (pinfunction "GND_GND") (pintype "bidirectional"))
      (node (ref "JP18") (pin "GNDBREAK") (pinfunction "GNDBREAK_GNDBREAK") (pintype "bidirectional"))
      (node (ref "JP2") (pin "GND1") (pinfunction "GND_GND1") (pintype "bidirectional"))
      (node (ref "JP3") (pin "1") (pinfunction "1_1") (pintype "passive"))
      (node (ref "JP6") (pin "2") (pinfunction "2_2") (pintype "passive"))
      (node (ref "JP6") (pin "3") (pinfunction "3_3") (pintype "passive"))
      (node (ref "JP7") (pin "7") (pinfunction "7_7") (pintype "passive"))
      (node (ref "JP8") (pin "11") (pinfunction "11_11") (pintype "passive"))
      (node (ref "JP8") (pin "12") (pinfunction "12_12") (pintype "passive"))
      (node (ref "JP9") (pin "11") (pinfunction "11_11") (pintype "passive"))
      (node (ref "JP9") (pin "12") (pinfunction "12_12") (pintype "passive"))
      (node (ref "R5") (pin "1") (pinfunction "1_1") (pintype "passive"))
      (node (ref "R6") (pin "1") (pinfunction "1_1") (pintype "passive"))
      (node (ref "S1") (pin "3") (pinfunction "2_3") (pintype "passive"))
      (node (ref "S2") (pin "3") (pinfunction "2_3") (pintype "passive"))
      (node (ref "S5") (pin "3") (pinfunction "2_3") (pintype "passive"))
      (node (ref "S6") (pin "3") (pinfunction "2_3") (pintype "passive"))
      (node (ref "U1") (pin "10") (pinfunction "VSSB_10") (pintype "bidirectional"))
      (node (ref "U1") (pin "12") (pinfunction "VBOOST_12") (pintype "bidirectional"))
      (node (ref "U1") (pin "13") (pinfunction "VBAT_13") (pintype "bidirectional"))
      (node (ref "U1") (pin "14") (pinfunction "VSSD0_14") (pintype "bidirectional"))
      (node (ref "U1") (pin "38") (pinfunction "VSSD1_38") (pintype "bidirectional"))
      (node (ref "U1") (pin "64") (pinfunction "VSSA_64") (pintype "bidirectional"))
      (node (ref "U1") (pin "66") (pinfunction "VSSD2_66") (pintype "bidirectional"))
      (node (ref "U1") (pin "87") (pinfunction "VSSD3_87") (pintype "bidirectional"))
      (node (ref "U2") (pin "2") (pinfunction "GND_2") (pintype "input"))
      (node (ref "U3") (pin "2") (pinfunction "GND_2") (pintype "input"))
      (node (ref "U7") (pin "25") (pinfunction "VSSD1_25") (pintype "bidirectional"))
      (node (ref "U7") (pin "43") (pinfunction "VSSA_43") (pintype "bidirectional"))
      (node (ref "U7") (pin "45") (pinfunction "VSSD2_45") (pintype "bidirectional"))
      (node (ref "U7") (pin "5") (pinfunction "VSSB_5") (pintype "bidirectional"))
      (node (ref "U7") (pin "54") (pinfunction "P0[5]_54") (pintype "bidirectional"))
      (node (ref "U7") (pin "56") (pinfunction "P0[7]_56") (pintype "bidirectional"))
      (node (ref "U7") (pin "58") (pinfunction "VSSD3_58") (pintype "bidirectional"))
      (node (ref "U7") (pin "69") (pinfunction "VSSD0_69") (pintype "bidirectional"))
      (node (ref "U7") (pin "7") (pinfunction "VBOOST_7") (pintype "bidirectional"))
      (node (ref "U7") (pin "8") (pinfunction "VBAT_8") (pintype "bidirectional"))
      (node (ref "U7") (pin "9") (pinfunction "VSSD0_9") (pintype "bidirectional"))
    )
    (net (code "48") (name "Net-(C26-Pad2)") (class "Default")
      (node (ref "C26") (pin "2") (pinfunction "2_2") (pintype "passive"))
      (node (ref "R11") (pin "1") (pinfunction "1_1") (pintype "passive"))
    )
    (net (code "49") (name "Net-(C28-Pad2)") (class "Default")
      (node (ref "C28") (pin "2") (pinfunction "2_2") (pintype "passive"))
      (node (ref "R12") (pin "1") (pinfunction "1_1") (pintype "passive"))
    )
    (net (code "50") (name "Net-(C34-Pad1)") (class "Default")
      (node (ref "C34") (pin "1") (pinfunction "1_1") (pintype "passive"))
      (node (ref "SJ5") (pin "2") (pinfunction "2_2") (pintype "passive"))
    )
    (net (code "51") (name "Net-(C35-Pad1)") (class "Default")
      (node (ref "C35") (pin "1") (pinfunction "1_1") (pintype "passive"))
      (node (ref "SJ4") (pin "2") (pinfunction "2_2") (pintype "passive"))
    )
    (net (code "52") (name "Net-(C36-Pad1)") (class "Default")
      (node (ref "C36") (pin "1") (pinfunction "1_1") (pintype "passive"))
      (node (ref "SJ3") (pin "2") (pinfunction "2_2") (pintype "passive"))
    )
    (net (code "53") (name "Net-(D1-PadC)") (class "Default")
      (node (ref "D1") (pin "C") (pinfunction "C_C") (pintype "passive"))
      (node (ref "D2") (pin "C") (pinfunction "C_C") (pintype "passive"))
      (node (ref "D3") (pin "C") (pinfunction "C_C") (pintype "passive"))
      (node (ref "SJ1") (pin "1") (pinfunction "1_1") (pintype "passive"))
    )
    (net (code "54") (name "Net-(D3-PadA)") (class "Default")
      (node (ref "D3") (pin "A") (pinfunction "A_A") (pintype "passive"))
      (node (ref "JP18") (pin "PWR") (pinfunction "PWR_PWR") (pintype "bidirectional"))
    )
    (net (code "55") (name "Net-(D4-PadA)") (class "Default")
      (node (ref "D4") (pin "A") (pinfunction "A_A") (pintype "passive"))
      (node (ref "JP3") (pin "2") (pinfunction "2_2") (pintype "passive"))
      (node (ref "SJ2") (pin "1") (pinfunction "1_1") (pintype "passive"))
    )
    (net (code "56") (name "Net-(D5-PadA)") (class "Default")
      (node (ref "D5") (pin "A") (pinfunction "A_A") (pintype "passive"))
      (node (ref "R21") (pin "2") (pinfunction "2_2") (pintype "passive"))
    )
    (net (code "57") (name "Net-(D6-PadA)") (class "Default")
      (node (ref "D6") (pin "A") (pinfunction "A_A") (pintype "passive"))
      (node (ref "R20") (pin "2") (pinfunction "2_2") (pintype "passive"))
    )
    (net (code "58") (name "Net-(U1E-P15[6])") (class "Default")
      (node (ref "R16") (pin "1") (pinfunction "1_1") (pintype "passive"))
      (node (ref "U1") (pin "35") (pinfunction "P15[6]_35") (pintype "bidirectional"))
    )
    (net (code "59") (name "Net-(U1E-P15[7])") (class "Default")
      (node (ref "R17") (pin "1") (pinfunction "1_1") (pintype "passive"))
      (node (ref "U1") (pin "36") (pinfunction "P15[7]_36") (pintype "bidirectional"))
    )
    (net (code "60") (name "Net-(U1E-VCCA)") (class "Default")
      (node (ref "C1") (pin "1") (pinfunction "1_1") (pintype "passive"))
      (node (ref "U1") (pin "63") (pinfunction "VCCA_63") (pintype "bidirectional"))
    )
    (net (code "61") (name "Net-(U1E-VCCD0)") (class "Default")
      (node (ref "C7") (pin "1") (pinfunction "1_1") (pintype "passive"))
      (node (ref "U1") (pin "39") (pinfunction "VCCD0_39") (pintype "bidirectional"))
      (node (ref "U1") (pin "86") (pinfunction "VCCD1_86") (pintype "bidirectional"))
    )
    (net (code "62") (name "Net-(U4A-S)") (class "Default")
      (node (ref "R7") (pin "1") (pinfunction "1_1") (pintype "passive"))
      (node (ref "U4") (pin "S1") (pinfunction "S_S1") (pintype "passive"))
    )
    (net (code "63") (name "Net-(U4B-S)") (class "Default")
      (node (ref "R8") (pin "1") (pinfunction "1_1") (pintype "passive"))
      (node (ref "U4") (pin "S2") (pinfunction "S_S2") (pintype "passive"))
    )
    (net (code "64") (name "Net-(U7E-P15[6])") (class "Default")
      (node (ref "R18") (pin "1") (pinfunction "1_1") (pintype "passive"))
      (node (ref "U7") (pin "22") (pinfunction "P15[6]_22") (pintype "bidirectional"))
    )
    (net (code "65") (name "Net-(U7E-P15[7])") (class "Default")
      (node (ref "R19") (pin "1") (pinfunction "1_1") (pintype "passive"))
      (node (ref "U7") (pin "23") (pinfunction "P15[7]_23") (pintype "bidirectional"))
    )
    (net (code "66") (name "Net-(U7E-VCCA)") (class "Default")
      (node (ref "C17") (pin "1") (pinfunction "1_1") (pintype "passive"))
      (node (ref "U7") (pin "42") (pinfunction "VCCA_42") (pintype "bidirectional"))
    )
    (net (code "67") (name "Net-(U7E-VCCD0)") (class "Default")
      (node (ref "C16") (pin "1") (pinfunction "1_1") (pintype "passive"))
      (node (ref "U7") (pin "26") (pinfunction "VCCD0_26") (pintype "bidirectional"))
      (node (ref "U7") (pin "57") (pinfunction "VCCD1_57") (pintype "bidirectional"))
    )
    (net (code "68") (name "P0.0") (class "Default")
      (node (ref "JP8") (pin "1") (pinfunction "1_1") (pintype "passive"))
      (node (ref "U1") (pin "71") (pinfunction "P0[0]_71") (pintype "bidirectional"))
    )
    (net (code "69") (name "P0.1") (class "Default")
      (node (ref "JP8") (pin "2") (pinfunction "2_2") (pintype "passive"))
      (node (ref "U1") (pin "72") (pinfunction "P0[1]_72") (pintype "bidirectional"))
    )
    (net (code "70") (name "P0.2") (class "Default")
      (node (ref "JP8") (pin "3") (pinfunction "3_3") (pintype "passive"))
      (node (ref "SJ3") (pin "1") (pinfunction "1_1") (pintype "passive"))
      (node (ref "U1") (pin "73") (pinfunction "P0[2]_73") (pintype "bidirectional"))
    )
    (net (code "71") (name "P0.3") (class "Default")
      (node (ref "JP8") (pin "4") (pinfunction "4_4") (pintype "passive"))
      (node (ref "SJ4") (pin "1") (pinfunction "1_1") (pintype "passive"))
      (node (ref "U1") (pin "74") (pinfunction "P0[3]_74") (pintype "bidirectional"))
    )
    (net (code "72") (name "P0.4") (class "Default")
      (node (ref "JP8") (pin "5") (pinfunction "5_5") (pintype "passive"))
      (node (ref "SJ5") (pin "1") (pinfunction "1_1") (pintype "passive"))
      (node (ref "U1") (pin "76") (pinfunction "P0[4]_76") (pintype "bidirectional"))
    )
    (net (code "73") (name "P0.5") (class "Default")
      (node (ref "JP8") (pin "6") (pinfunction "6_6") (pintype "passive"))
      (node (ref "U1") (pin "77") (pinfunction "P0[5]_77") (pintype "bidirectional"))
    )
    (net (code "74") (name "P0.6") (class "Default")
      (node (ref "JP8") (pin "7") (pinfunction "7_7") (pintype "passive"))
      (node (ref "U1") (pin "78") (pinfunction "P0[6]_78") (pintype "bidirectional"))
    )
    (net (code "75") (name "P0.7") (class "Default")
      (node (ref "JP8") (pin "8") (pinfunction "8_8") (pintype "passive"))
      (node (ref "U1") (pin "79") (pinfunction "P0[7]_79") (pintype "bidirectional"))
    )
    (net (code "76") (name "P1.0") (class "Default")
      (node (ref "JP17") (pin "2") (pinfunction "2_2") (pintype "passive"))
      (node (ref "U1") (pin "20") (pinfunction "P1[0]_20") (pintype "bidirectional"))
      (node (ref "U7") (pin "46") (pinfunction "P12[2]_46") (pintype "bidirectional"))
    )
    (net (code "77") (name "P1.1") (class "Default")
      (node (ref "JP17") (pin "4") (pinfunction "4_4") (pintype "passive"))
      (node (ref "U1") (pin "21") (pinfunction "P1[1]_21") (pintype "bidirectional"))
      (node (ref "U7") (pin "47") (pinfunction "P12[3]_47") (pintype "bidirectional"))
    )
    (net (code "78") (name "P1.2") (class "Default")
      (node (ref "S6") (pin "1") (pinfunction "1_1") (pintype "passive"))
      (node (ref "U1") (pin "22") (pinfunction "P1[2]_22") (pintype "bidirectional"))
    )
    (net (code "79") (name "P1.3") (class "Default")
      (node (ref "JP17") (pin "6") (pinfunction "6_6") (pintype "passive"))
      (node (ref "U1") (pin "23") (pinfunction "P1[3]_23") (pintype "bidirectional"))
    )
    (net (code "80") (name "P1.4") (class "Default")
      (node (ref "JP17") (pin "8") (pinfunction "8_8") (pintype "passive"))
      (node (ref "U1") (pin "24") (pinfunction "P1[4]_24") (pintype "bidirectional"))
    )
    (net (code "81") (name "P3.0") (class "Default")
      (node (ref "JP12") (pin "1") (pinfunction "1_1") (pintype "passive"))
      (node (ref "U1") (pin "44") (pinfunction "P3[0]_44") (pintype "bidirectional"))
    )
    (net (code "82") (name "P3.1") (class "Default")
      (node (ref "JP12") (pin "2") (pinfunction "2_2") (pintype "passive"))
      (node (ref "U1") (pin "45") (pinfunction "P3[1]_45") (pintype "bidirectional"))
    )
    (net (code "83") (name "P3.2") (class "Default")
      (node (ref "JP12") (pin "3") (pinfunction "3_3") (pintype "passive"))
      (node (ref "U1") (pin "46") (pinfunction "P3[2]_46") (pintype "bidirectional"))
    )
    (net (code "84") (name "P3.3") (class "Default")
      (node (ref "JP12") (pin "4") (pinfunction "4_4") (pintype "passive"))
      (node (ref "U1") (pin "47") (pinfunction "P3[3]_47") (pintype "bidirectional"))
    )
    (net (code "85") (name "P3.4") (class "Default")
      (node (ref "JP12") (pin "5") (pinfunction "5_5") (pintype "passive"))
      (node (ref "U1") (pin "48") (pinfunction "P3[4]_48") (pintype "bidirectional"))
    )
    (net (code "86") (name "P3.5") (class "Default")
      (node (ref "JP12") (pin "6") (pinfunction "6_6") (pintype "passive"))
      (node (ref "U1") (pin "49") (pinfunction "P3[5]_49") (pintype "bidirectional"))
    )
    (net (code "87") (name "P3.6") (class "Default")
      (node (ref "JP12") (pin "7") (pinfunction "7_7") (pintype "passive"))
      (node (ref "U1") (pin "51") (pinfunction "P3[6]_51") (pintype "bidirectional"))
    )
    (net (code "88") (name "P3.7") (class "Default")
      (node (ref "JP12") (pin "8") (pinfunction "8_8") (pintype "passive"))
      (node (ref "U1") (pin "52") (pinfunction "P3[7]_52") (pintype "bidirectional"))
    )
    (net (code "89") (name "P4.0") (class "Default")
      (node (ref "JP9") (pin "2") (pinfunction "2_2") (pintype "passive"))
      (node (ref "U1") (pin "69") (pinfunction "P4[0]_69") (pintype "bidirectional"))
    )
    (net (code "90") (name "P4.1") (class "Default")
      (node (ref "JP9") (pin "1") (pinfunction "1_1") (pintype "passive"))
      (node (ref "U1") (pin "70") (pinfunction "P4[1]_70") (pintype "bidirectional"))
    )
    (net (code "91") (name "P4.2") (class "Default")
      (node (ref "JP9") (pin "4") (pinfunction "4_4") (pintype "passive"))
      (node (ref "U1") (pin "80") (pinfunction "P4[2]_80") (pintype "bidirectional"))
    )
    (net (code "92") (name "P4.3") (class "Default")
      (node (ref "JP9") (pin "3") (pinfunction "3_3") (pintype "passive"))
      (node (ref "U1") (pin "81") (pinfunction "P4[3]_81") (pintype "bidirectional"))
    )
    (net (code "93") (name "P4.4") (class "Default")
      (node (ref "JP9") (pin "6") (pinfunction "6_6") (pintype "passive"))
      (node (ref "U1") (pin "82") (pinfunction "P4[4]_82") (pintype "bidirectional"))
    )
    (net (code "94") (name "P4.5") (class "Default")
      (node (ref "JP9") (pin "5") (pinfunction "5_5") (pintype "passive"))
      (node (ref "U1") (pin "83") (pinfunction "P4[5]_83") (pintype "bidirectional"))
    )
    (net (code "95") (name "P4.6") (class "Default")
      (node (ref "JP9") (pin "8") (pinfunction "8_8") (pintype "passive"))
      (node (ref "U1") (pin "84") (pinfunction "P4[6]_84") (pintype "bidirectional"))
    )
    (net (code "96") (name "P4.7") (class "Default")
      (node (ref "JP9") (pin "7") (pinfunction "7_7") (pintype "passive"))
      (node (ref "U1") (pin "85") (pinfunction "P4[7]_85") (pintype "bidirectional"))
    )
    (net (code "97") (name "P5.0") (class "Default")
      (node (ref "JP11") (pin "2") (pinfunction "2_2") (pintype "passive"))
      (node (ref "U1") (pin "16") (pinfunction "P5[0]_16") (pintype "bidirectional"))
    )
    (net (code "98") (name "P5.1") (class "Default")
      (node (ref "JP11") (pin "1") (pinfunction "1_1") (pintype "passive"))
      (node (ref "U1") (pin "17") (pinfunction "P5[1]_17") (pintype "bidirectional"))
    )
    (net (code "99") (name "P5.2") (class "Default")
      (node (ref "JP11") (pin "4") (pinfunction "4_4") (pintype "passive"))
      (node (ref "U1") (pin "18") (pinfunction "P5[2]_18") (pintype "bidirectional"))
    )
    (net (code "100") (name "P5.3") (class "Default")
      (node (ref "JP11") (pin "3") (pinfunction "3_3") (pintype "passive"))
      (node (ref "U1") (pin "19") (pinfunction "P5[3]_19") (pintype "bidirectional"))
    )
    (net (code "101") (name "P5.4") (class "Default")
      (node (ref "JP11") (pin "6") (pinfunction "6_6") (pintype "passive"))
      (node (ref "U1") (pin "31") (pinfunction "P5[4]_31") (pintype "bidirectional"))
    )
    (net (code "102") (name "P5.5") (class "Default")
      (node (ref "JP11") (pin "5") (pinfunction "5_5") (pintype "passive"))
      (node (ref "U1") (pin "32") (pinfunction "P5[5]_32") (pintype "bidirectional"))
    )
    (net (code "103") (name "P5.6") (class "Default")
      (node (ref "JP11") (pin "8") (pinfunction "8_8") (pintype "passive"))
      (node (ref "U1") (pin "33") (pinfunction "P5[6]_33") (pintype "bidirectional"))
    )
    (net (code "104") (name "P5.7") (class "Default")
      (node (ref "JP11") (pin "7") (pinfunction "7_7") (pintype "passive"))
      (node (ref "U1") (pin "34") (pinfunction "P5[7]_34") (pintype "bidirectional"))
    )
    (net (code "105") (name "P12.0") (class "Default")
      (node (ref "JP10") (pin "3") (pinfunction "3_3") (pintype "passive"))
      (node (ref "U1") (pin "53") (pinfunction "P12[0]_53") (pintype "bidirectional"))
    )
    (net (code "106") (name "P12.1") (class "Default")
      (node (ref "JP10") (pin "4") (pinfunction "4_4") (pintype "passive"))
      (node (ref "U1") (pin "54") (pinfunction "P12[1]_54") (pintype "bidirectional"))
    )
    (net (code "107") (name "P12.2") (class "Default")
      (node (ref "JP10") (pin "5") (pinfunction "5_5") (pintype "passive"))
      (node (ref "U1") (pin "67") (pinfunction "P12[2]_67") (pintype "bidirectional"))
    )
    (net (code "108") (name "P12.3") (class "Default")
      (node (ref "JP10") (pin "6") (pinfunction "6_6") (pintype "passive"))
      (node (ref "U1") (pin "68") (pinfunction "P12[3]_68") (pintype "bidirectional"))
    )
    (net (code "109") (name "P12.6") (class "Default")
      (node (ref "JP10") (pin "7") (pinfunction "7_7") (pintype "passive"))
      (node (ref "U1") (pin "29") (pinfunction "P12[6]_29") (pintype "bidirectional"))
    )
    (net (code "110") (name "P12.7") (class "Default")
      (node (ref "JP10") (pin "8") (pinfunction "8_8") (pintype "passive"))
      (node (ref "U1") (pin "30") (pinfunction "P12[7]_30") (pintype "bidirectional"))
    )
    (net (code "111") (name "P15.0") (class "Default")
      (node (ref "C14") (pin "1") (pinfunction "1_1") (pintype "passive"))
      (node (ref "U1") (pin "42") (pinfunction "P15[0]_42") (pintype "bidirectional"))
      (node (ref "Y2") (pin "1") (pinfunction "1_1") (pintype "passive"))
    )
    (net (code "112") (name "P15.1") (class "Default")
      (node (ref "C12") (pin "1") (pinfunction "1_1") (pintype "passive"))
      (node (ref "U1") (pin "43") (pinfunction "P15[1]_43") (pintype "bidirectional"))
      (node (ref "Y2") (pin "2") (pinfunction "2_2") (pintype "passive"))
    )
    (net (code "113") (name "P15.2") (class "Default")
      (node (ref "C18") (pin "1") (pinfunction "1_1") (pintype "passive"))
      (node (ref "U1") (pin "55") (pinfunction "P15[2]_55") (pintype "bidirectional"))
      (node (ref "Y1") (pin "2") (pinfunction "2_2") (pintype "passive"))
    )
    (net (code "114") (name "P15.3") (class "Default")
      (node (ref "C24") (pin "1") (pinfunction "1_1") (pintype "passive"))
      (node (ref "U1") (pin "56") (pinfunction "P15[3]_56") (pintype "bidirectional"))
      (node (ref "Y1") (pin "1") (pinfunction "1_1") (pintype "passive"))
    )
    (net (code "115") (name "PSOC_D+_BUS") (class "Default")
      (node (ref "JP1") (pin "D+1") (pinfunction "D+_D+1") (pintype "bidirectional"))
      (node (ref "R16") (pin "2") (pinfunction "2_2") (pintype "passive"))
    )
    (net (code "116") (name "PSOC_D-_BUS") (class "Default")
      (node (ref "JP1") (pin "D-1") (pinfunction "D-_D-1") (pintype "bidirectional"))
      (node (ref "R17") (pin "2") (pinfunction "2_2") (pintype "passive"))
    )
    (net (code "117") (name "VDDIO") (class "Default")
      (node (ref "C13") (pin "1") (pinfunction "1_1") (pintype "passive"))
      (node (ref "C15") (pin "1") (pinfunction "1_1") (pintype "passive"))
      (node (ref "C25") (pin "1") (pinfunction "1_1") (pintype "passive"))
      (node (ref "C27") (pin "1") (pinfunction "1_1") (pintype "passive"))
      (node (ref "C29") (pin "1") (pinfunction "1_1") (pintype "passive"))
      (node (ref "C31") (pin "1") (pinfunction "1_1") (pintype "passive"))
      (node (ref "C9") (pin "1") (pinfunction "1_1") (pintype "passive"))
      (node (ref "JP10") (pin "2") (pinfunction "2_2") (pintype "passive"))
      (node (ref "JP11") (pin "10") (pinfunction "10_10") (pintype "passive"))
      (node (ref "JP11") (pin "9") (pinfunction "9_9") (pintype "passive"))
      (node (ref "JP12") (pin "10") (pinfunction "10_10") (pintype "passive"))
      (node (ref "JP12") (pin "9") (pinfunction "9_9") (pintype "passive"))
      (node (ref "JP14") (pin "1") (pinfunction "1_1") (pintype "passive"))
      (node (ref "JP15") (pin "1") (pinfunction "1_1") (pintype "passive"))
      (node (ref "JP17") (pin "1") (pinfunction "1_1") (pintype "passive"))
      (node (ref "JP8") (pin "10") (pinfunction "10_10") (pintype "passive"))
      (node (ref "JP8") (pin "9") (pinfunction "9_9") (pintype "passive"))
      (node (ref "JP9") (pin "10") (pinfunction "10_10") (pintype "passive"))
      (node (ref "JP9") (pin "9") (pinfunction "9_9") (pintype "passive"))
      (node (ref "R7") (pin "2") (pinfunction "2_2") (pintype "passive"))
      (node (ref "R8") (pin "2") (pinfunction "2_2") (pintype "passive"))
      (node (ref "S4") (pin "2") (pinfunction "P_2") (pintype "passive"))
      (node (ref "U1") (pin "26") (pinfunction "VDDIO1_26") (pintype "bidirectional"))
      (node (ref "U1") (pin "50") (pinfunction "VDDIO3_50") (pintype "bidirectional"))
      (node (ref "U1") (pin "75") (pinfunction "VDDIO0_75") (pintype "bidirectional"))
      (node (ref "U7") (pin "17") (pinfunction "VDDIO1_17") (pintype "bidirectional"))
      (node (ref "U7") (pin "35") (pinfunction "VDDIO3_35") (pintype "bidirectional"))
      (node (ref "U7") (pin "52") (pinfunction "VDDIO0_52") (pintype "bidirectional"))
      (node (ref "U7") (pin "67") (pinfunction "VDDIO2_67") (pintype "bidirectional"))
    )
    (net (code "118") (name "VDDIO_ARDUINO") (class "Default")
      (node (ref "C11") (pin "1") (pinfunction "1_1") (pintype "passive"))
      (node (ref "JP13") (pin "2") (pinfunction "2_2") (pintype "bidirectional"))
      (node (ref "JP6") (pin "7") (pinfunction "7_7") (pintype "passive"))
      (node (ref "S3") (pin "2") (pinfunction "P_2") (pintype "passive"))
      (node (ref "U1") (pin "100") (pinfunction "VDDIO2_100") (pintype "bidirectional"))
    )
    (net (code "119") (name "V_BUS_DEBUG") (class "Default")
      (node (ref "R4") (pin "2") (pinfunction "2_2") (pintype "passive"))
      (node (ref "R5") (pin "2") (pinfunction "2_2") (pintype "passive"))
      (node (ref "U7") (pin "18") (pinfunction "P1[6]_18") (pintype "bidirectional"))
    )
    (net (code "120") (name "V_BUS_HOST") (class "Default")
      (node (ref "R3") (pin "2") (pinfunction "2_2") (pintype "passive"))
      (node (ref "R6") (pin "2") (pinfunction "2_2") (pintype "passive"))
      (node (ref "U1") (pin "27") (pinfunction "P1[6]_27") (pintype "bidirectional"))
    )
    (net (code "121") (name "V_DEBUG") (class "Default")
      (node (ref "D2") (pin "A") (pinfunction "A_A") (pintype "passive"))
      (node (ref "JP2") (pin "VBUS1") (pinfunction "VCC_VBUS1") (pintype "bidirectional"))
      (node (ref "R4") (pin "1") (pinfunction "1_1") (pintype "passive"))
    )
    (net (code "122") (name "V_HOST") (class "Default")
      (node (ref "D1") (pin "A") (pinfunction "A_A") (pintype "passive"))
      (node (ref "JP1") (pin "VBUS1") (pinfunction "VCC_VBUS1") (pintype "bidirectional"))
      (node (ref "R3") (pin "1") (pinfunction "1_1") (pintype "passive"))
    )
    (net (code "123") (name "V_IN") (class "Default")
      (node (ref "C37") (pin "1") (pinfunction "1_1") (pintype "passive"))
      (node (ref "C38") (pin "1") (pinfunction "1_1") (pintype "passive"))
      (node (ref "D4") (pin "C") (pinfunction "C_C") (pintype "passive"))
      (node (ref "JP6") (pin "1") (pinfunction "1_1") (pintype "passive"))
      (node (ref "SJ1") (pin "2") (pinfunction "2_2") (pintype "passive"))
      (node (ref "SJ2") (pin "2") (pinfunction "2_2") (pintype "passive"))
      (node (ref "U2") (pin "1") (pinfunction "IN_1") (pintype "input"))
      (node (ref "U2") (pin "3") (pinfunction "EN_3") (pintype "input"))
      (node (ref "U3") (pin "1") (pinfunction "IN_1") (pintype "input"))
      (node (ref "U3") (pin "3") (pinfunction "EN_3") (pintype "input"))
    )
    (net (code "124") (name "unconnected-(JP1-ID-PadID1)") (class "Default")
      (node (ref "JP1") (pin "ID1") (pinfunction "ID_ID1") (pintype "bidirectional"))
    )
    (net (code "125") (name "unconnected-(JP2-ID-PadID1)") (class "Default")
      (node (ref "JP2") (pin "ID1") (pinfunction "ID_ID1") (pintype "bidirectional"))
    )
    (net (code "126") (name "unconnected-(JP6-Pad8)") (class "Default")
      (node (ref "JP6") (pin "8") (pinfunction "8_8") (pintype "passive"))
    )
    (net (code "127") (name "unconnected-(JP7-Pad8)") (class "Default")
      (node (ref "JP7") (pin "8") (pinfunction "8_8") (pintype "passive"))
    )
    (net (code "128") (name "unconnected-(U1B-P1[5]-Pad25)") (class "Default")
      (node (ref "U1") (pin "25") (pinfunction "P1[5]_25") (pintype "bidirectional"))
    )
    (net (code "129") (name "unconnected-(U1B-P1[7]-Pad28)") (class "Default")
      (node (ref "U1") (pin "28") (pinfunction "P1[7]_28") (pintype "bidirectional"))
    )
    (net (code "130") (name "unconnected-(U1E-IND-Pad11)") (class "Default")
      (node (ref "U1") (pin "11") (pinfunction "IND_11") (pintype "bidirectional"))
    )
    (net (code "131") (name "unconnected-(U2-BP-Pad4)") (class "Default")
      (node (ref "U2") (pin "4") (pinfunction "BP_4") (pintype "input"))
    )
    (net (code "132") (name "unconnected-(U3-BP-Pad4)") (class "Default")
      (node (ref "U3") (pin "4") (pinfunction "BP_4") (pintype "input"))
    )
    (net (code "133") (name "unconnected-(U7A-P0[6]-Pad55)") (class "Default")
      (node (ref "U7") (pin "55") (pinfunction "P0[6]_55") (pintype "bidirectional"))
    )
    (net (code "134") (name "unconnected-(U7B-P1[5]-Pad16)") (class "Default")
      (node (ref "U7") (pin "16") (pinfunction "P1[5]_16") (pintype "bidirectional"))
    )
    (net (code "135") (name "unconnected-(U7B-P1[7]-Pad19)") (class "Default")
      (node (ref "U7") (pin "19") (pinfunction "P1[7]_19") (pintype "bidirectional"))
    )
    (net (code "136") (name "unconnected-(U7C-P2[0]-Pad62)") (class "Default")
      (node (ref "U7") (pin "62") (pinfunction "P2[0]_62") (pintype "bidirectional"))
    )
    (net (code "137") (name "unconnected-(U7C-P2[1]-Pad63)") (class "Default")
      (node (ref "U7") (pin "63") (pinfunction "P2[1]_63") (pintype "bidirectional"))
    )
    (net (code "138") (name "unconnected-(U7C-P2[3]-Pad65)") (class "Default")
      (node (ref "U7") (pin "65") (pinfunction "P2[3]_65") (pintype "bidirectional"))
    )
    (net (code "139") (name "unconnected-(U7C-P2[4]-Pad66)") (class "Default")
      (node (ref "U7") (pin "66") (pinfunction "P2[4]_66") (pintype "bidirectional"))
    )
    (net (code "140") (name "unconnected-(U7C-P2[5]-Pad68)") (class "Default")
      (node (ref "U7") (pin "68") (pinfunction "P2[5]_68") (pintype "bidirectional"))
    )
    (net (code "141") (name "unconnected-(U7C-P12[5]-Pad4)") (class "Default")
      (node (ref "U7") (pin "4") (pinfunction "P12[5]_4") (pintype "bidirectional"))
    )
    (net (code "142") (name "unconnected-(U7C-P15[4]-Pad60)") (class "Default")
      (node (ref "U7") (pin "60") (pinfunction "P15[4]_60") (pintype "bidirectional"))
    )
    (net (code "143") (name "unconnected-(U7C-P15[5]-Pad61)") (class "Default")
      (node (ref "U7") (pin "61") (pinfunction "P15[5]_61") (pintype "bidirectional"))
    )
    (net (code "144") (name "unconnected-(U7D-P3[2]-Pad31)") (class "Default")
      (node (ref "U7") (pin "31") (pinfunction "P3[2]_31") (pintype "bidirectional"))
    )
    (net (code "145") (name "unconnected-(U7D-P3[3]-Pad32)") (class "Default")
      (node (ref "U7") (pin "32") (pinfunction "P3[3]_32") (pintype "bidirectional"))
    )
    (net (code "146") (name "unconnected-(U7D-P15[0]-Pad27)") (class "Default")
      (node (ref "U7") (pin "27") (pinfunction "P15[0]_27") (pintype "bidirectional"))
    )
    (net (code "147") (name "unconnected-(U7D-P15[1]-Pad28)") (class "Default")
      (node (ref "U7") (pin "28") (pinfunction "P15[1]_28") (pintype "bidirectional"))
    )
    (net (code "148") (name "unconnected-(U7D-P15[2]-Pad40)") (class "Default")
      (node (ref "U7") (pin "40") (pinfunction "P15[2]_40") (pintype "bidirectional"))
    )
    (net (code "149") (name "unconnected-(U7D-P15[3]-Pad41)") (class "Default")
      (node (ref "U7") (pin "41") (pinfunction "P15[3]_41") (pintype "bidirectional"))
    )
    (net (code "150") (name "unconnected-(U7E-IND-Pad6)") (class "Default")
      (node (ref "U7") (pin "6") (pinfunction "IND_6") (pintype "bidirectional"))
    )
    (net (code "151") (name "~{DEBUG_P2.6_SCL_PU_EN}") (class "Default")
      (node (ref "U4") (pin "G2") (pinfunction "G_G2") (pintype "passive"))
      (node (ref "U7") (pin "1") (pinfunction "P2[6]_1") (pintype "bidirectional"))
    )
    (net (code "152") (name "~{DEBUG_P2.7_SDA_PU_EN}") (class "Default")
      (node (ref "U4") (pin "G1") (pinfunction "G_G1") (pintype "passive"))
      (node (ref "U7") (pin "2") (pinfunction "P2[7]_2") (pintype "bidirectional"))
    )
    (net (code "153") (name "~{DEBUG_RESET}") (class "Default")
      (node (ref "JP14") (pin "10") (pinfunction "10_10") (pintype "passive"))
      (node (ref "R2") (pin "1") (pinfunction "1_1") (pintype "passive"))
      (node (ref "S1") (pin "1") (pinfunction "1_1") (pintype "passive"))
      (node (ref "U7") (pin "10") (pinfunction "~{XRES}_10") (pintype "bidirectional"))
    )
    (net (code "154") (name "~{RESET}") (class "Default")
      (node (ref "JP13") (pin "5") (pinfunction "5_5") (pintype "bidirectional"))
      (node (ref "JP17") (pin "10") (pinfunction "10_10") (pintype "passive"))
      (node (ref "JP6") (pin "6") (pinfunction "6_6") (pintype "passive"))
      (node (ref "R1") (pin "1") (pinfunction "1_1") (pintype "passive"))
      (node (ref "S2") (pin "1") (pinfunction "1_1") (pintype "passive"))
      (node (ref "U1") (pin "15") (pinfunction "~{XRES}_15") (pintype "bidirectional"))
      (node (ref "U7") (pin "3") (pinfunction "P12[4]_3") (pintype "bidirectional"))
    )
  )
)
